# ETHER.net
KiCad netlist of a schematic drawn in Altium Designer
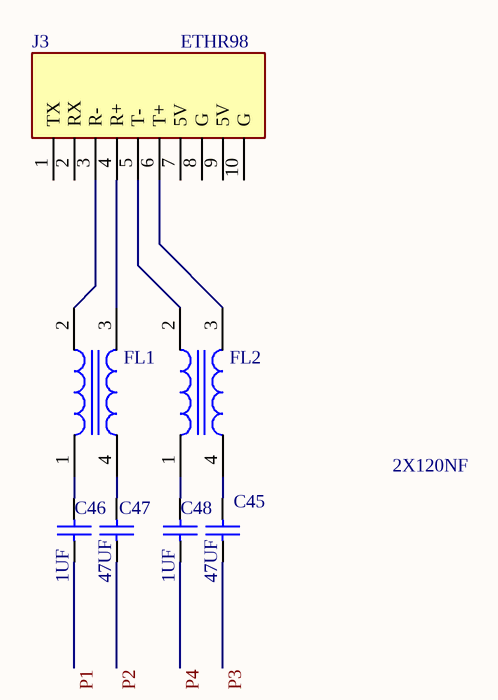
[diagram p0: ETHER.SchDoc]

(export (version "E")
  (design (tool "Eeschema 10.0.6"))
  (components
    (comp (ref "C45")
      (value "47UF")
      (footprint "CAPC1005X56X25LL10T15")
      (libsource (lib "Altium Content Vault") (part "CAP"))
    )
    (comp (ref "C46")
      (value "1UF")
      (footprint "CAPC1005X56X25LL10T15")
      (libsource (lib "Altium Content Vault") (part "CAP"))
    )
    (comp (ref "C47")
      (value "47UF")
      (footprint "CAPC1005X56X25LL10T15")
      (libsource (lib "Altium Content Vault") (part "CAP"))
    )
    (comp (ref "C48")
      (value "1UF")
      (footprint "CAPC1005X56X25LL10T15")
      (libsource (lib "Altium Content Vault") (part "CAP"))
    )
    (comp (ref "FL1")
      (value "B82789C0513N002")
      (footprint "FL_B82789C0513N002")
      (description "51 ÂµH @ 100 kHz 2 Line Common Mode Choke Surface Mount 250mA DCR 550mOhm")
      (fields (field (name "MF") "EPCOS"))
      (libsource (lib "B82789C0513N002") (part "B82789C0513N002"))
    )
    (comp (ref "FL2")
      (value "B82789C0513N002")
      (footprint "FL_B82789C0513N002")
      (description "51 ÂµH @ 100 kHz 2 Line Common Mode Choke Surface Mount 250mA DCR 550mOhm")
      (fields (field (name "MF") "EPCOS"))
      (libsource (lib "B82789C0513N002") (part "B82789C0513N002"))
    )
    (comp (ref "J3") (value "ETHR98") (libsource (lib "Schlib1") (part "ETHR98")))
  )
  (nets
    (net (code "1") (name "/P1") (class "Default")
      (node (ref "C46") (pin "1") (pinfunction "1_1") (pintype "passive"))
    )
    (net (code "2") (name "/P2") (class "Default")
      (node (ref "C47") (pin "1") (pinfunction "1_1") (pintype "passive"))
    )
    (net (code "3") (name "/P3") (class "Default")
      (node (ref "C45") (pin "1") (pinfunction "1_1") (pintype "passive"))
    )
    (net (code "4") (name "/P4") (class "Default")
      (node (ref "C48") (pin "1") (pinfunction "1_1") (pintype "passive"))
    )
    (net (code "5") (name "Net-(C45-Pad2)") (class "Default")
      (node (ref "C45") (pin "2") (pinfunction "2_2") (pintype "passive"))
      (node (ref "FL2") (pin "4") (pinfunction "4_4") (pintype "passive"))
    )
    (net (code "6") (name "Net-(C46-Pad2)") (class "Default")
      (node (ref "C46") (pin "2") (pinfunction "2_2") (pintype "passive"))
      (node (ref "FL1") (pin "1") (pinfunction "1_1") (pintype "passive"))
    )
    (net (code "7") (name "Net-(C47-Pad2)") (class "Default")
      (node (ref "C47") (pin "2") (pinfunction "2_2") (pintype "passive"))
      (node (ref "FL1") (pin "4") (pinfunction "4_4") (pintype "passive"))
    )
    (net (code "8") (name "Net-(C48-Pad2)") (class "Default")
      (node (ref "C48") (pin "2") (pinfunction "2_2") (pintype "passive"))
      (node (ref "FL2") (pin "1") (pinfunction "1_1") (pintype "passive"))
    )
    (net (code "9") (name "Net-(J3-R+)") (class "Default")
      (node (ref "FL1") (pin "3") (pinfunction "3_3") (pintype "passive"))
      (node (ref "J3") (pin "4") (pinfunction "R+_4") (pintype "passive"))
    )
    (net (code "10") (name "Net-(J3-R-)") (class "Default")
      (node (ref "FL1") (pin "2") (pinfunction "2_2") (pintype "passive"))
      (node (ref "J3") (pin "3") (pinfunction "R-_3") (pintype "passive"))
    )
    (net (code "11") (name "Net-(J3-T+)") (class "Default")
      (node (ref "FL2") (pin "3") (pinfunction "3_3") (pintype "passive"))
      (node (ref "J3") (pin "6") (pinfunction "T+_6") (pintype "passive"))
    )
    (net (code "12") (name "Net-(J3-T-)") (class "Default")
      (node (ref "FL2") (pin "2") (pinfunction "2_2") (pintype "passive"))
      (node (ref "J3") (pin "5") (pinfunction "T-_5") (pintype "passive"))
    )
    (net (code "13") (name "unconnected-(J3-5V-Pad7)") (class "Default")
      (node (ref "J3") (pin "7") (pinfunction "5V_7") (pintype "passive"))
    )
    (net (code "14") (name "unconnected-(J3-5V-Pad9)") (class "Default")
      (node (ref "J3") (pin "9") (pinfunction "5V_9") (pintype "passive"))
    )
    (net (code "15") (name "unconnected-(J3-G-Pad8)") (class "Default")
      (node (ref "J3") (pin "8") (pinfunction "G_8") (pintype "passive"))
    )
    (net (code "16") (name "unconnected-(J3-G-Pad10)") (class "Default")
      (node (ref "J3") (pin "10") (pinfunction "G_10") (pintype "passive"))
    )
    (net (code "17") (name "unconnected-(J3-RX-Pad2)") (class "Default")
      (node (ref "J3") (pin "2") (pinfunction "RX_2") (pintype "passive"))
    )
    (net (code "18") (name "unconnected-(J3-TX-Pad1)") (class "Default")
      (node (ref "J3") (pin "1") (pinfunction "TX_1") (pintype "passive"))
    )
  )
)
